# utility.net
KiCad netlist of a schematic drawn in Altium Designer
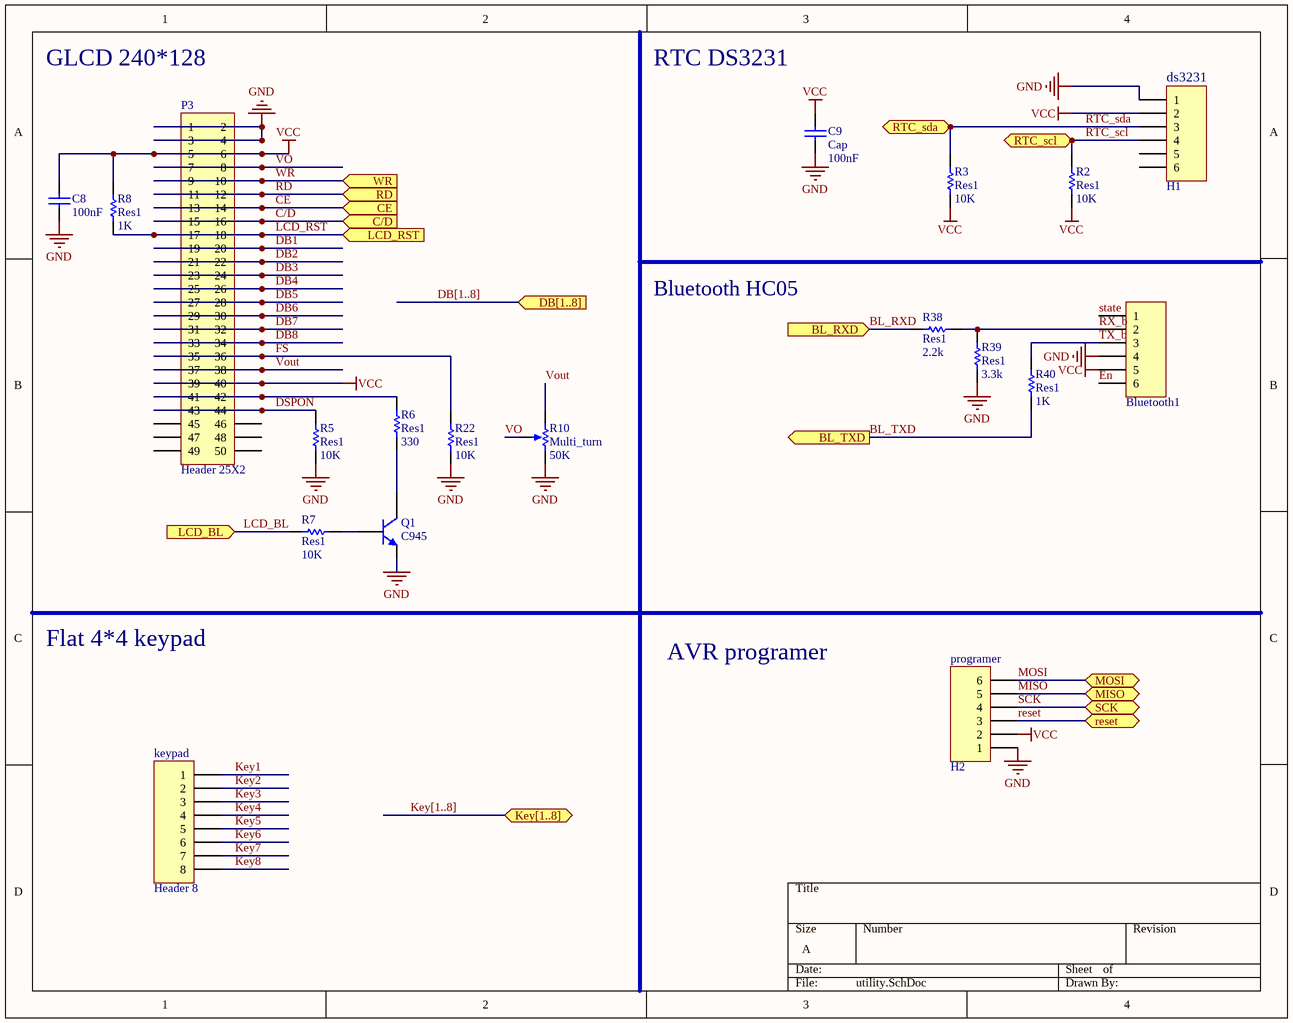
[diagram p0: utility.SchDoc]

(export (version "E")
  (design (tool "Eeschema 10.0.6"))
  (components
    (comp (ref "Bluetooth1")
      (value "H-1x6")
      (footprint "H-1x6")
      (libsource (lib "Mine-Discreet") (part "H-1x6"))
    )
    (comp (ref "C8")
      (value "100nF")
      (footprint "CAP 1206 (3216X15L)")
      (description "CAP-100Nf")
      (fields (field (name "Comment") "Cap"))
      (libsource (lib "Altium library (www.AVRelec.com)") (part "Cap ceramic"))
    )
    (comp (ref "C9")
      (value "Cap")
      (footprint "CAP 1206 (3216X15L)")
      (description "CAP-100Nf")
      (fields (field (name "ALTIUM_VALUE") "100nF"))
      (libsource (lib "Altium library (www.AVRelec.com)") (part "Cap ceramic"))
    )
    (comp (ref "H1") (value "H-1x6") (footprint "ds3231") (libsource (lib "Mine-Discreet") (part "H-1x6")))
    (comp (ref "H2") (value "programer") (footprint "HDR1X6") (libsource (lib "") (part "H-1x6_1")))
    (comp (ref "keypad")
      (value "Header 8")
      (footprint "HDR1X8")
      (description "Header, 8-Pin")
      (fields (field (name "PUBLISHER") "Altium Limited"))
      (libsource (lib "Miscellaneous Connectors") (part "Header 8"))
    )
    (comp (ref "P3")
      (value "Header 25X2")
      (footprint "HDR2X25")
      (description "Header, 25-Pin, Dual row")
      (fields (field (name "PUBLISHER") "Altium Limited"))
      (libsource (lib "Miscellaneous Connectors") (part "Header 25X2"))
    )
    (comp (ref "Q1")
      (value "C945")
      (footprint "SOT23_N")
      (description "NPN Silicon Epitaxial Planar Transistor")
      (fields (field (name "PUBLISHER") "Abbas Basereh"))
      (libsource (lib "Altium (2)") (part "C945"))
    )
    (comp (ref "R2")
      (value "Res1")
      (footprint "RES 1206 (3216X08L)")
      (description "Resistor")
      (fields (field (name "ALTIUM_VALUE") "10K") (field (name "PUBLISHER") "Altium Limited"))
      (libsource (lib "Miscellaneous Devices") (part "Res1"))
    )
    (comp (ref "R3")
      (value "Res1")
      (footprint "RES 1206 (3216X08L)")
      (description "Resistor")
      (fields (field (name "ALTIUM_VALUE") "10K") (field (name "PUBLISHER") "Altium Limited"))
      (libsource (lib "Miscellaneous Devices") (part "Res1"))
    )
    (comp (ref "R5")
      (value "Res1")
      (footprint "RES 1206 (3216X08L)")
      (description "Resistor")
      (fields (field (name "ALTIUM_VALUE") "10K") (field (name "PUBLISHER") "Altium Limited"))
      (libsource (lib "Miscellaneous Devices") (part "Res1"))
    )
    (comp (ref "R6")
      (value "Res1")
      (footprint "RES 1206 (3216X08L)")
      (description "Resistor")
      (fields (field (name "ALTIUM_VALUE") "330") (field (name "PUBLISHER") "Altium Limited"))
      (libsource (lib "Miscellaneous Devices") (part "Res1"))
    )
    (comp (ref "R7")
      (value "Res1")
      (footprint "RES 1206 (3216X08L)")
      (description "Resistor")
      (fields (field (name "ALTIUM_VALUE") "10K") (field (name "PUBLISHER") "Altium Limited"))
      (libsource (lib "Miscellaneous Devices") (part "Res1"))
    )
    (comp (ref "R8")
      (value "Res1")
      (footprint "RES 1206 (3216X08L)")
      (description "Resistor")
      (fields (field (name "ALTIUM_VALUE") "1K") (field (name "PUBLISHER") "Altium Limited"))
      (libsource (lib "Miscellaneous Devices") (part "Res1"))
    )
    (comp (ref "R10")
      (value "Multi_turn")
      (footprint "Multi Turn 02")
      (description "Potentiometer")
      (fields (field (name "ALTIUM_VALUE") "50K") (field (name "PUBLISHER") "Altium Limited"))
      (libsource (lib "Altium library (www.AVRelec.com)") (part "Multi_turn"))
    )
    (comp (ref "R22")
      (value "Res1")
      (footprint "RES 1206 (3216X08L)")
      (description "Resistor")
      (fields (field (name "ALTIUM_VALUE") "10K") (field (name "PUBLISHER") "Altium Limited"))
      (libsource (lib "Miscellaneous Devices") (part "Res1"))
    )
    (comp (ref "R38")
      (value "Res1")
      (footprint "RES 1206 (3216X08L)")
      (description "Resistor")
      (fields (field (name "ALTIUM_VALUE") "2.2k") (field (name "PUBLISHER") "Altium Limited"))
      (libsource (lib "Miscellaneous Devices") (part "Res1"))
    )
    (comp (ref "R39")
      (value "Res1")
      (footprint "RES 1206 (3216X08L)")
      (description "Resistor")
      (fields (field (name "ALTIUM_VALUE") "3.3k") (field (name "PUBLISHER") "Altium Limited"))
      (libsource (lib "Miscellaneous Devices") (part "Res1"))
    )
    (comp (ref "R40")
      (value "Res1")
      (footprint "RES 1206 (3216X08L)")
      (description "Resistor")
      (fields (field (name "ALTIUM_VALUE") "1K") (field (name "PUBLISHER") "Altium Limited"))
      (libsource (lib "Miscellaneous Devices") (part "Res1"))
    )
  )
  (nets
    (net (code "1") (name "/BL_RXD") (class "Default")
      (node (ref "R38") (pin "1") (pinfunction "1_1") (pintype "passive"))
    )
    (net (code "2") (name "/BL_TXD") (class "Default")
      (node (ref "R40") (pin "2") (pinfunction "2_2") (pintype "passive"))
    )
    (net (code "3") (name "/CE") (class "Default")
      (node (ref "P3") (pin "13") (pinfunction "13_13") (pintype "passive"))
      (node (ref "P3") (pin "14") (pinfunction "14_14") (pintype "passive"))
    )
    (net (code "4") (name "/C{slash}D") (class "Default")
      (node (ref "P3") (pin "15") (pinfunction "15_15") (pintype "passive"))
      (node (ref "P3") (pin "16") (pinfunction "16_16") (pintype "passive"))
    )
    (net (code "5") (name "/DB1") (class "Default")
      (node (ref "P3") (pin "19") (pinfunction "19_19") (pintype "passive"))
      (node (ref "P3") (pin "20") (pinfunction "20_20") (pintype "passive"))
    )
    (net (code "6") (name "/DB2") (class "Default")
      (node (ref "P3") (pin "21") (pinfunction "21_21") (pintype "passive"))
      (node (ref "P3") (pin "22") (pinfunction "22_22") (pintype "passive"))
    )
    (net (code "7") (name "/DB3") (class "Default")
      (node (ref "P3") (pin "23") (pinfunction "23_23") (pintype "passive"))
      (node (ref "P3") (pin "24") (pinfunction "24_24") (pintype "passive"))
    )
    (net (code "8") (name "/DB4") (class "Default")
      (node (ref "P3") (pin "25") (pinfunction "25_25") (pintype "passive"))
      (node (ref "P3") (pin "26") (pinfunction "26_26") (pintype "passive"))
    )
    (net (code "9") (name "/DB5") (class "Default")
      (node (ref "P3") (pin "27") (pinfunction "27_27") (pintype "passive"))
      (node (ref "P3") (pin "28") (pinfunction "28_28") (pintype "passive"))
    )
    (net (code "10") (name "/DB6") (class "Default")
      (node (ref "P3") (pin "29") (pinfunction "29_29") (pintype "passive"))
      (node (ref "P3") (pin "30") (pinfunction "30_30") (pintype "passive"))
    )
    (net (code "11") (name "/DB7") (class "Default")
      (node (ref "P3") (pin "31") (pinfunction "31_31") (pintype "passive"))
      (node (ref "P3") (pin "32") (pinfunction "32_32") (pintype "passive"))
    )
    (net (code "12") (name "/DB8") (class "Default")
      (node (ref "P3") (pin "33") (pinfunction "33_33") (pintype "passive"))
      (node (ref "P3") (pin "34") (pinfunction "34_34") (pintype "passive"))
    )
    (net (code "14") (name "/DSPON") (class "Default")
      (node (ref "P3") (pin "43") (pinfunction "43_43") (pintype "passive"))
      (node (ref "P3") (pin "44") (pinfunction "44_44") (pintype "passive"))
      (node (ref "R5") (pin "2") (pinfunction "2_2") (pintype "passive"))
    )
    (net (code "15") (name "/En") (class "Default")
      (node (ref "Bluetooth1") (pin "6") (pinfunction "6_6") (pintype "passive"))
    )
    (net (code "16") (name "/FS") (class "Default")
      (node (ref "P3") (pin "35") (pinfunction "35_35") (pintype "passive"))
      (node (ref "P3") (pin "36") (pinfunction "36_36") (pintype "passive"))
      (node (ref "R22") (pin "2") (pinfunction "2_2") (pintype "passive"))
    )
    (net (code "17") (name "/Key1") (class "Default")
      (node (ref "keypad") (pin "1") (pinfunction "1_1") (pintype "passive"))
    )
    (net (code "18") (name "/Key2") (class "Default")
      (node (ref "keypad") (pin "2") (pinfunction "2_2") (pintype "passive"))
    )
    (net (code "19") (name "/Key3") (class "Default")
      (node (ref "keypad") (pin "3") (pinfunction "3_3") (pintype "passive"))
    )
    (net (code "20") (name "/Key4") (class "Default")
      (node (ref "keypad") (pin "4") (pinfunction "4_4") (pintype "passive"))
    )
    (net (code "21") (name "/Key5") (class "Default")
      (node (ref "keypad") (pin "5") (pinfunction "5_5") (pintype "passive"))
    )
    (net (code "22") (name "/Key6") (class "Default")
      (node (ref "keypad") (pin "6") (pinfunction "6_6") (pintype "passive"))
    )
    (net (code "23") (name "/Key7") (class "Default")
      (node (ref "keypad") (pin "7") (pinfunction "7_7") (pintype "passive"))
    )
    (net (code "24") (name "/Key8") (class "Default")
      (node (ref "keypad") (pin "8") (pinfunction "8_8") (pintype "passive"))
    )
    (net (code "26") (name "/LCD_BL") (class "Default")
      (node (ref "R7") (pin "2") (pinfunction "2_2") (pintype "passive"))
    )
    (net (code "27") (name "/LCD_RST") (class "Default")
      (node (ref "P3") (pin "17") (pinfunction "17_17") (pintype "passive"))
      (node (ref "P3") (pin "18") (pinfunction "18_18") (pintype "passive"))
      (node (ref "R8") (pin "2") (pinfunction "2_2") (pintype "passive"))
    )
    (net (code "28") (name "/MISO") (class "Default")
      (node (ref "H2") (pin "5") (pinfunction "5_5") (pintype "passive"))
    )
    (net (code "29") (name "/MOSI") (class "Default")
      (node (ref "H2") (pin "6") (pinfunction "6_6") (pintype "passive"))
    )
    (net (code "30") (name "/RD") (class "Default")
      (node (ref "P3") (pin "11") (pinfunction "11_11") (pintype "passive"))
      (node (ref "P3") (pin "12") (pinfunction "12_12") (pintype "passive"))
    )
    (net (code "31") (name "/RTC_scl") (class "Default")
      (node (ref "H1") (pin "4") (pinfunction "4_4") (pintype "passive"))
      (node (ref "R2") (pin "2") (pinfunction "2_2") (pintype "passive"))
    )
    (net (code "32") (name "/RTC_sda") (class "Default")
      (node (ref "H1") (pin "3") (pinfunction "3_3") (pintype "passive"))
      (node (ref "R3") (pin "2") (pinfunction "2_2") (pintype "passive"))
    )
    (net (code "33") (name "/RX_b") (class "Default")
      (node (ref "Bluetooth1") (pin "2") (pinfunction "2_2") (pintype "passive"))
      (node (ref "R38") (pin "2") (pinfunction "2_2") (pintype "passive"))
      (node (ref "R39") (pin "2") (pinfunction "2_2") (pintype "passive"))
    )
    (net (code "34") (name "/SCK") (class "Default")
      (node (ref "H2") (pin "4") (pinfunction "4_4") (pintype "passive"))
    )
    (net (code "35") (name "/TX_b") (class "Default")
      (node (ref "Bluetooth1") (pin "3") (pinfunction "3_3") (pintype "passive"))
      (node (ref "R40") (pin "1") (pinfunction "1_1") (pintype "passive"))
    )
    (net (code "36") (name "/VO") (class "Default")
      (node (ref "P3") (pin "7") (pinfunction "7_7") (pintype "passive"))
      (node (ref "P3") (pin "8") (pinfunction "8_8") (pintype "passive"))
      (node (ref "R10") (pin "3") (pinfunction "TAP_3") (pintype "passive"))
    )
    (net (code "37") (name "/Vout") (class "Default")
      (node (ref "P3") (pin "37") (pinfunction "37_37") (pintype "passive"))
      (node (ref "P3") (pin "38") (pinfunction "38_38") (pintype "passive"))
      (node (ref "R10") (pin "1") (pinfunction "TOP_1") (pintype "passive"))
    )
    (net (code "38") (name "/WR") (class "Default")
      (node (ref "P3") (pin "10") (pinfunction "10_10") (pintype "passive"))
      (node (ref "P3") (pin "9") (pinfunction "9_9") (pintype "passive"))
    )
    (net (code "39") (name "/reset") (class "Default")
      (node (ref "H2") (pin "3") (pinfunction "3_3") (pintype "passive"))
    )
    (net (code "40") (name "/state") (class "Default")
      (node (ref "Bluetooth1") (pin "1") (pinfunction "1_1") (pintype "passive"))
    )
    (net (code "41") (name "GND") (class "Default")
      (node (ref "Bluetooth1") (pin "4") (pinfunction "4_4") (pintype "passive"))
      (node (ref "C8") (pin "1") (pinfunction "1_1") (pintype "passive"))
      (node (ref "C9") (pin "1") (pinfunction "1_1") (pintype "passive"))
      (node (ref "H1") (pin "1") (pinfunction "1_1") (pintype "passive"))
      (node (ref "H2") (pin "1") (pinfunction "1_1") (pintype "passive"))
      (node (ref "P3") (pin "1") (pinfunction "1_1") (pintype "passive"))
      (node (ref "P3") (pin "2") (pinfunction "2_2") (pintype "passive"))
      (node (ref "P3") (pin "3") (pinfunction "3_3") (pintype "passive"))
      (node (ref "P3") (pin "4") (pinfunction "4_4") (pintype "passive"))
      (node (ref "Q1") (pin "2") (pinfunction "E_2") (pintype "passive"))
      (node (ref "R10") (pin "2") (pinfunction "BOT_2") (pintype "passive"))
      (node (ref "R22") (pin "1") (pinfunction "1_1") (pintype "passive"))
      (node (ref "R39") (pin "1") (pinfunction "1_1") (pintype "passive"))
      (node (ref "R5") (pin "1") (pinfunction "1_1") (pintype "passive"))
    )
    (net (code "42") (name "Net-(P3-Pad41)") (class "Default")
      (node (ref "P3") (pin "41") (pinfunction "41_41") (pintype "passive"))
      (node (ref "P3") (pin "42") (pinfunction "42_42") (pintype "passive"))
      (node (ref "R6") (pin "2") (pinfunction "2_2") (pintype "passive"))
    )
    (net (code "43") (name "Net-(Q1-B)") (class "Default")
      (node (ref "Q1") (pin "1") (pinfunction "B_1") (pintype "passive"))
      (node (ref "R7") (pin "1") (pinfunction "1_1") (pintype "passive"))
    )
    (net (code "44") (name "Net-(Q1-C)") (class "Default")
      (node (ref "Q1") (pin "3") (pinfunction "C_3") (pintype "passive"))
      (node (ref "R6") (pin "1") (pinfunction "1_1") (pintype "passive"))
    )
    (net (code "45") (name "VCC") (class "Default")
      (node (ref "Bluetooth1") (pin "5") (pinfunction "5_5") (pintype "passive"))
      (node (ref "C8") (pin "2") (pinfunction "2_2") (pintype "passive"))
      (node (ref "C9") (pin "2") (pinfunction "2_2") (pintype "passive"))
      (node (ref "H1") (pin "2") (pinfunction "2_2") (pintype "passive"))
      (node (ref "H2") (pin "2") (pinfunction "2_2") (pintype "passive"))
      (node (ref "P3") (pin "39") (pinfunction "39_39") (pintype "passive"))
      (node (ref "P3") (pin "40") (pinfunction "40_40") (pintype "passive"))
      (node (ref "P3") (pin "5") (pinfunction "5_5") (pintype "passive"))
      (node (ref "P3") (pin "6") (pinfunction "6_6") (pintype "passive"))
      (node (ref "R2") (pin "1") (pinfunction "1_1") (pintype "passive"))
      (node (ref "R3") (pin "1") (pinfunction "1_1") (pintype "passive"))
      (node (ref "R8") (pin "1") (pinfunction "1_1") (pintype "passive"))
    )
    (net (code "46") (name "unconnected-(H1-Pad5)") (class "Default")
      (node (ref "H1") (pin "5") (pinfunction "5_5") (pintype "passive"))
    )
    (net (code "47") (name "unconnected-(H1-Pad6)") (class "Default")
      (node (ref "H1") (pin "6") (pinfunction "6_6") (pintype "passive"))
    )
    (net (code "48") (name "unconnected-(P3-Pad45)") (class "Default")
      (node (ref "P3") (pin "45") (pinfunction "45_45") (pintype "passive"))
    )
    (net (code "49") (name "unconnected-(P3-Pad46)") (class "Default")
      (node (ref "P3") (pin "46") (pinfunction "46_46") (pintype "passive"))
    )
    (net (code "50") (name "unconnected-(P3-Pad47)") (class "Default")
      (node (ref "P3") (pin "47") (pinfunction "47_47") (pintype "passive"))
    )
    (net (code "51") (name "unconnected-(P3-Pad48)") (class "Default")
      (node (ref "P3") (pin "48") (pinfunction "48_48") (pintype "passive"))
    )
    (net (code "52") (name "unconnected-(P3-Pad49)") (class "Default")
      (node (ref "P3") (pin "49") (pinfunction "49_49") (pintype "passive"))
    )
    (net (code "53") (name "unconnected-(P3-Pad50)") (class "Default")
      (node (ref "P3") (pin "50") (pinfunction "50_50") (pintype "passive"))
    )
  )
)
